# Etapa_Control.net
KiCad netlist of a schematic drawn in EAGLE
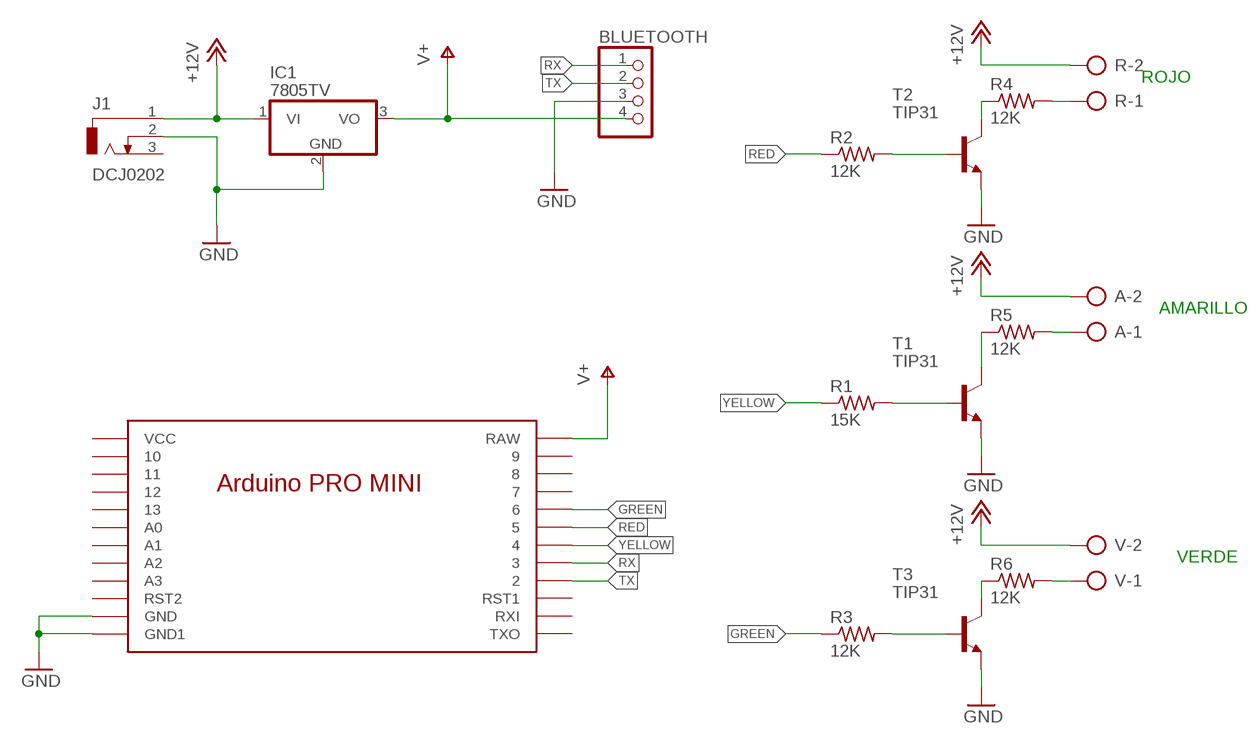
[diagram p0: schematic, sheet 1]

(export (version "E")
  (design (tool "Eeschema 10.0.6"))
  (components
    (comp (ref "A")
      (value "AK300/2")
      (footprint "eagle-import:AK300_2")
      (libsource (lib "eagle-import") (part "AK300/2"))
    )
    (comp (ref "BLUETOOTH")
      (value "PINHD-1X4")
      (footprint "eagle-import:1X04")
      (libsource (lib "eagle-import") (part "PINHD-1X4"))
    )
    (comp (ref "IC1")
      (value "7805TV")
      (footprint "eagle-import:TO220V")
      (libsource (lib "eagle-import") (part "78TV05"))
    )
    (comp (ref "J1")
      (value "DCJ0202")
      (footprint "eagle-import:DCJ0202")
      (libsource (lib "eagle-import") (part "DCJ0202"))
    )
    (comp (ref "R")
      (value "AK300/2")
      (footprint "eagle-import:AK300_2")
      (libsource (lib "eagle-import") (part "AK300/2"))
    )
    (comp (ref "R1")
      (value "15K")
      (footprint "eagle-import:0204_7")
      (libsource (lib "eagle-import") (part "R-US_0204/7"))
    )
    (comp (ref "R2")
      (value "12K")
      (footprint "eagle-import:0204_7")
      (libsource (lib "eagle-import") (part "R-US_0204/7"))
    )
    (comp (ref "R3")
      (value "12K")
      (footprint "eagle-import:0204_7")
      (libsource (lib "eagle-import") (part "R-US_0204/7"))
    )
    (comp (ref "R4")
      (value "12K")
      (footprint "eagle-import:0204_7")
      (libsource (lib "eagle-import") (part "R-US_0204/7"))
    )
    (comp (ref "R5")
      (value "12K")
      (footprint "eagle-import:0204_7")
      (libsource (lib "eagle-import") (part "R-US_0204/7"))
    )
    (comp (ref "R6")
      (value "12K")
      (footprint "eagle-import:0204_7")
      (libsource (lib "eagle-import") (part "R-US_0204/7"))
    )
    (comp (ref "T1")
      (value "TIP31")
      (footprint "eagle-import:TO220")
      (libsource (lib "eagle-import") (part "TIP31"))
    )
    (comp (ref "T2")
      (value "TIP31")
      (footprint "eagle-import:TO220")
      (libsource (lib "eagle-import") (part "TIP31"))
    )
    (comp (ref "T3")
      (value "TIP31")
      (footprint "eagle-import:TO220")
      (libsource (lib "eagle-import") (part "TIP31"))
    )
    (comp (ref "U$1")
      (value "NANO")
      (footprint "eagle-import:NANO")
      (libsource (lib "eagle-import") (part "NANO"))
    )
    (comp (ref "V")
      (value "AK300/2")
      (footprint "eagle-import:AK300_2")
      (libsource (lib "eagle-import") (part "AK300/2"))
    )
  )
  (nets
    (net (code "1") (name "+12V") (class "Default")
      (node (ref "A") (pin "2") (pinfunction "KL_2") (pintype "passive"))
      (node (ref "IC1") (pin "1") (pinfunction "VI_1") (pintype "input"))
      (node (ref "J1") (pin "1") (pinfunction "1_1") (pintype "passive"))
      (node (ref "R") (pin "2") (pinfunction "KL_2") (pintype "passive"))
      (node (ref "V") (pin "2") (pinfunction "KL_2") (pintype "passive"))
    )
    (net (code "2") (name "GND") (class "Default")
      (node (ref "BLUETOOTH") (pin "3") (pinfunction "3_3") (pintype "passive"))
      (node (ref "IC1") (pin "2") (pinfunction "GND_2") (pintype "passive"))
      (node (ref "J1") (pin "2") (pinfunction "2_2") (pintype "passive"))
      (node (ref "T1") (pin "3") (pinfunction "E_3") (pintype "passive"))
      (node (ref "T2") (pin "3") (pinfunction "E_3") (pintype "passive"))
      (node (ref "T3") (pin "3") (pinfunction "E_3") (pintype "passive"))
      (node (ref "U$1") (pin "GND1") (pinfunction "GND_GND1") (pintype "bidirectional"))
      (node (ref "U$1") (pin "GND2") (pinfunction "GND1_GND2") (pintype "power_in"))
    )
    (net (code "3") (name "GREEN") (class "Default")
      (node (ref "R3") (pin "1") (pinfunction "1_1") (pintype "passive"))
      (node (ref "U$1") (pin "6") (pinfunction "6_6") (pintype "bidirectional"))
    )
    (net (code "4") (name "Net-(AA-KL)") (class "Default")
      (node (ref "A") (pin "1") (pinfunction "KL_1") (pintype "passive"))
      (node (ref "R5") (pin "2") (pinfunction "2_2") (pintype "passive"))
    )
    (net (code "5") (name "Net-(RA-KL)") (class "Default")
      (node (ref "R") (pin "1") (pinfunction "KL_1") (pintype "passive"))
      (node (ref "R4") (pin "2") (pinfunction "2_2") (pintype "passive"))
    )
    (net (code "6") (name "Net-(T1-B)") (class "Default")
      (node (ref "R1") (pin "2") (pinfunction "2_2") (pintype "passive"))
      (node (ref "T1") (pin "1") (pinfunction "B_1") (pintype "passive"))
    )
    (net (code "7") (name "Net-(T1-C)") (class "Default")
      (node (ref "R5") (pin "1") (pinfunction "1_1") (pintype "passive"))
      (node (ref "T1") (pin "2") (pinfunction "C_2") (pintype "passive"))
    )
    (net (code "8") (name "Net-(T2-B)") (class "Default")
      (node (ref "R2") (pin "2") (pinfunction "2_2") (pintype "passive"))
      (node (ref "T2") (pin "1") (pinfunction "B_1") (pintype "passive"))
    )
    (net (code "9") (name "Net-(T2-C)") (class "Default")
      (node (ref "R4") (pin "1") (pinfunction "1_1") (pintype "passive"))
      (node (ref "T2") (pin "2") (pinfunction "C_2") (pintype "passive"))
    )
    (net (code "10") (name "Net-(T3-B)") (class "Default")
      (node (ref "R3") (pin "2") (pinfunction "2_2") (pintype "passive"))
      (node (ref "T3") (pin "1") (pinfunction "B_1") (pintype "passive"))
    )
    (net (code "11") (name "Net-(T3-C)") (class "Default")
      (node (ref "R6") (pin "1") (pinfunction "1_1") (pintype "passive"))
      (node (ref "T3") (pin "2") (pinfunction "C_2") (pintype "passive"))
    )
    (net (code "12") (name "Net-(VA-KL)") (class "Default")
      (node (ref "R6") (pin "2") (pinfunction "2_2") (pintype "passive"))
      (node (ref "V") (pin "1") (pinfunction "KL_1") (pintype "passive"))
    )
    (net (code "13") (name "RED") (class "Default")
      (node (ref "R2") (pin "1") (pinfunction "1_1") (pintype "passive"))
      (node (ref "U$1") (pin "5") (pinfunction "5_5") (pintype "bidirectional"))
    )
    (net (code "14") (name "RX") (class "Default")
      (node (ref "BLUETOOTH") (pin "1") (pinfunction "1_1") (pintype "passive"))
      (node (ref "U$1") (pin "3") (pinfunction "3_3") (pintype "bidirectional"))
    )
    (net (code "15") (name "TX") (class "Default")
      (node (ref "BLUETOOTH") (pin "2") (pinfunction "2_2") (pintype "passive"))
      (node (ref "U$1") (pin "2") (pinfunction "2_2") (pintype "bidirectional"))
    )
    (net (code "16") (name "V+") (class "Default")
      (node (ref "BLUETOOTH") (pin "4") (pinfunction "4_4") (pintype "passive"))
      (node (ref "IC1") (pin "3") (pinfunction "VO_3") (pintype "passive"))
      (node (ref "U$1") (pin "RAW") (pinfunction "RAW_RAW") (pintype "bidirectional"))
    )
    (net (code "17") (name "YELLOW") (class "Default")
      (node (ref "R1") (pin "1") (pinfunction "1_1") (pintype "passive"))
      (node (ref "U$1") (pin "4") (pinfunction "4_4") (pintype "bidirectional"))
    )
    (net (code "18") (name "unconnected-(J1-Pad3)") (class "Default")
      (node (ref "J1") (pin "3") (pinfunction "3_3") (pintype "passive"))
    )
    (net (code "19") (name "unconnected-(U$1-Pad7)") (class "Default")
      (node (ref "U$1") (pin "7") (pinfunction "7_7") (pintype "bidirectional"))
    )
    (net (code "20") (name "unconnected-(U$1-Pad8)") (class "Default")
      (node (ref "U$1") (pin "8") (pinfunction "8_8") (pintype "bidirectional"))
    )
    (net (code "21") (name "unconnected-(U$1-Pad9)") (class "Default")
      (node (ref "U$1") (pin "9") (pinfunction "9_9") (pintype "bidirectional"))
    )
    (net (code "22") (name "unconnected-(U$1-Pad10)") (class "Default")
      (node (ref "U$1") (pin "10") (pinfunction "10_10") (pintype "bidirectional"))
    )
    (net (code "23") (name "unconnected-(U$1-Pad11)") (class "Default")
      (node (ref "U$1") (pin "11") (pinfunction "11_11") (pintype "bidirectional"))
    )
    (net (code "24") (name "unconnected-(U$1-Pad12)") (class "Default")
      (node (ref "U$1") (pin "12") (pinfunction "12_12") (pintype "bidirectional"))
    )
    (net (code "25") (name "unconnected-(U$1-Pad13)") (class "Default")
      (node (ref "U$1") (pin "13") (pinfunction "13_13") (pintype "bidirectional"))
    )
    (net (code "26") (name "unconnected-(U$1-PadA0)") (class "Default")
      (node (ref "U$1") (pin "A0") (pinfunction "A0_A0") (pintype "bidirectional"))
    )
    (net (code "27") (name "unconnected-(U$1-PadA1)") (class "Default")
      (node (ref "U$1") (pin "A1") (pinfunction "A1_A1") (pintype "bidirectional"))
    )
    (net (code "28") (name "unconnected-(U$1-PadA2)") (class "Default")
      (node (ref "U$1") (pin "A2") (pinfunction "A2_A2") (pintype "bidirectional"))
    )
    (net (code "29") (name "unconnected-(U$1-PadA3)") (class "Default")
      (node (ref "U$1") (pin "A3") (pinfunction "A3_A3") (pintype "bidirectional"))
    )
    (net (code "30") (name "unconnected-(U$1-PadRST1)") (class "Default")
      (node (ref "U$1") (pin "RST1") (pinfunction "RST1_RST1") (pintype "bidirectional"))
    )
    (net (code "31") (name "unconnected-(U$1-PadRST2)") (class "Default")
      (node (ref "U$1") (pin "RST2") (pinfunction "RST2_RST2") (pintype "bidirectional"))
    )
    (net (code "32") (name "unconnected-(U$1-PadRXI)") (class "Default")
      (node (ref "U$1") (pin "RXI") (pinfunction "RXI_RXI") (pintype "bidirectional"))
    )
    (net (code "33") (name "unconnected-(U$1-PadTXO)") (class "Default")
      (node (ref "U$1") (pin "TXO") (pinfunction "TXO_TXO") (pintype "bidirectional"))
    )
    (net (code "34") (name "unconnected-(U$1-PadVCC)") (class "Default")
      (node (ref "U$1") (pin "VCC") (pinfunction "VCC_VCC") (pintype "bidirectional"))
    )
  )
)
